# ADR_LEDs.net
KiCad netlist of a schematic drawn in Altium Designer
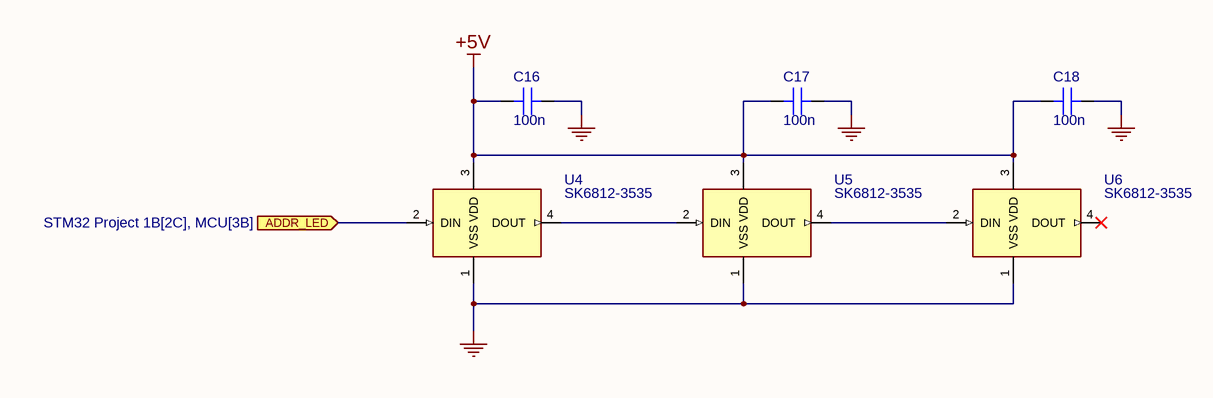
[diagram p0: ADR_LEDs.SchDoc]

(export (version "E")
  (design (tool "Eeschema 10.0.6"))
  (components
    (comp (ref "C16")
      (value "100n")
      (footprint "CAP_0805")
      (description "Capacitor SMD 0805 Generic")
      (libsource (lib "Generic-Schematic-Library") (part "CAP_0805"))
    )
    (comp (ref "C17")
      (value "100n")
      (footprint "CAP_0805")
      (description "Capacitor SMD 0805 Generic")
      (libsource (lib "Generic-Schematic-Library") (part "CAP_0805"))
    )
    (comp (ref "C18")
      (value "100n")
      (footprint "CAP_0805")
      (description "Capacitor SMD 0805 Generic")
      (libsource (lib "Generic-Schematic-Library") (part "CAP_0805"))
    )
    (comp (ref "U4")
      (value "SK6812-3535")
      (footprint "SK6812-3535")
      (description "NeoPixel 5050 RGB LED with Integrated Driver Chip - 10 Pack ¦ Adafruit Industries 1655")
      (fields
        (field (name "MANUFACTURER") "Adafruit Industries")
        (field (name "MANUFACTURER PART NUMBER") "1655")
      )
      (libsource (lib "Generic-Schematic-Library") (part "SK6812-3535"))
    )
    (comp (ref "U5")
      (value "SK6812-3535")
      (footprint "SK6812-3535")
      (description "NeoPixel 5050 RGB LED with Integrated Driver Chip - 10 Pack ¦ Adafruit Industries 1655")
      (fields
        (field (name "MANUFACTURER") "Adafruit Industries")
        (field (name "MANUFACTURER PART NUMBER") "1655")
      )
      (libsource (lib "Generic-Schematic-Library") (part "SK6812-3535"))
    )
    (comp (ref "U6")
      (value "SK6812-3535")
      (footprint "SK6812-3535")
      (description "NeoPixel 5050 RGB LED with Integrated Driver Chip - 10 Pack ¦ Adafruit Industries 1655")
      (fields
        (field (name "MANUFACTURER") "Adafruit Industries")
        (field (name "MANUFACTURER PART NUMBER") "1655")
      )
      (libsource (lib "Generic-Schematic-Library") (part "SK6812-3535"))
    )
  )
  (nets
    (net (code "1") (name "+5V") (class "Default")
      (node (ref "C16") (pin "2") (pintype "passive"))
      (node (ref "C17") (pin "2") (pintype "passive"))
      (node (ref "C18") (pin "2") (pintype "passive"))
      (node (ref "U4") (pin "3") (pinfunction "VDD_3") (pintype "power_in"))
      (node (ref "U5") (pin "3") (pinfunction "VDD_3") (pintype "power_in"))
      (node (ref "U6") (pin "3") (pinfunction "VDD_3") (pintype "power_in"))
    )
    (net (code "2") (name "/ADDR_LED") (class "Default")
      (node (ref "U4") (pin "2") (pinfunction "DIN_2") (pintype "input"))
    )
    (net (code "3") (name "GND") (class "Default")
      (node (ref "C16") (pin "1") (pintype "passive"))
      (node (ref "C17") (pin "1") (pintype "passive"))
      (node (ref "C18") (pin "1") (pintype "passive"))
      (node (ref "U4") (pin "1") (pinfunction "VSS_1") (pintype "power_in"))
      (node (ref "U5") (pin "1") (pinfunction "VSS_1") (pintype "power_in"))
      (node (ref "U6") (pin "1") (pinfunction "VSS_1") (pintype "power_in"))
    )
    (net (code "4") (name "Net-(U4-DOUT)") (class "Default")
      (node (ref "U4") (pin "4") (pinfunction "DOUT_4") (pintype "output"))
      (node (ref "U5") (pin "2") (pinfunction "DIN_2") (pintype "input"))
    )
    (net (code "5") (name "Net-(U5-DOUT)") (class "Default")
      (node (ref "U5") (pin "4") (pinfunction "DOUT_4") (pintype "output"))
      (node (ref "U6") (pin "2") (pinfunction "DIN_2") (pintype "input"))
    )
    (net (code "6") (name "unconnected-(U6-DOUT-Pad4)") (class "Default")
      (node (ref "U6") (pin "4") (pinfunction "DOUT_4") (pintype "output+no_connect"))
    )
  )
)
